# uno-level-shifter-v2.net
KiCad netlist of a schematic drawn in EAGLE
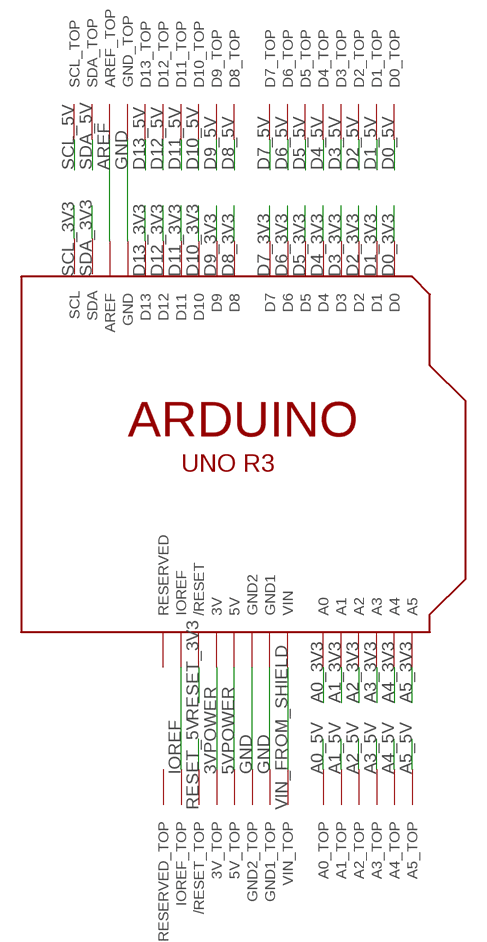
[diagram p0: schematic, sheet 1]
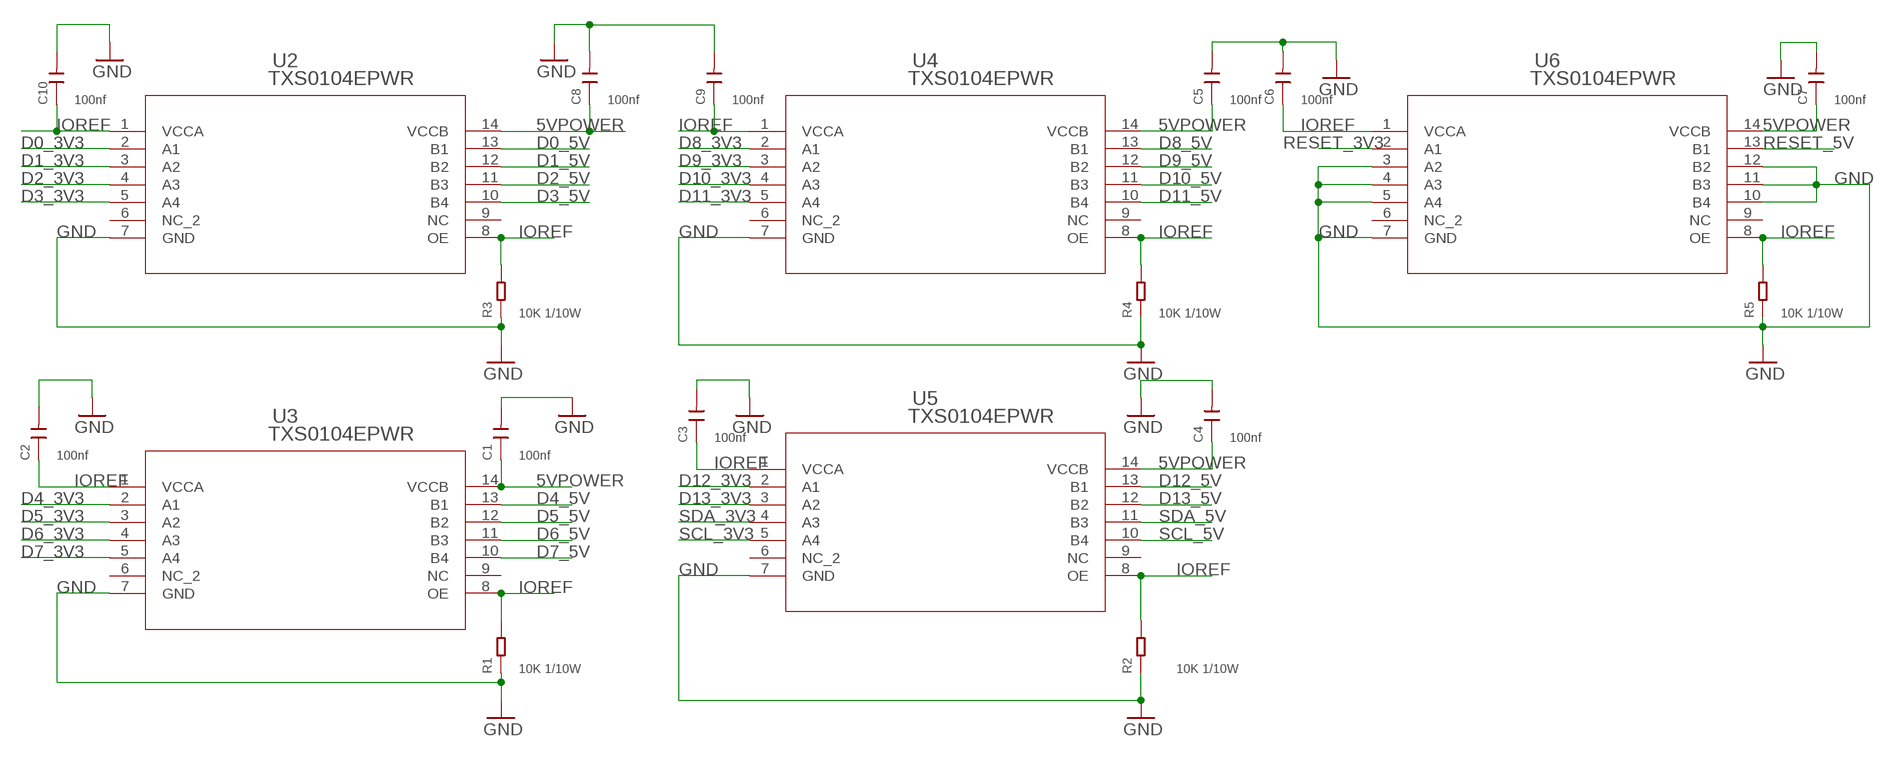
[diagram p1: schematic, sheet 2]
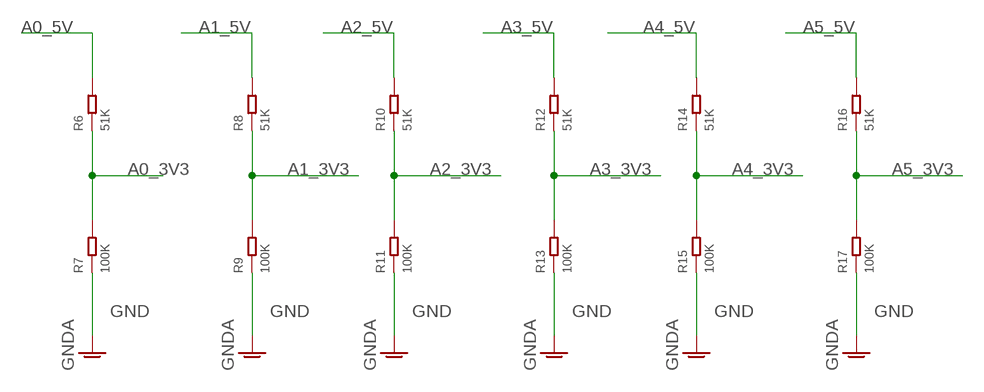
[diagram p2: schematic, sheet 3]

(export (version "E")
  (design (tool "Eeschema 10.0.6"))
  (components
    (comp (ref "R6")
      (value "51K")
      (footprint "eagle-import:R0603")
      (fields (field (name "MPN") "RC0603FR-071K5L"))
      (libsource (lib "eagle-import") (part "SMD-RES-51K-1%-1/10W(0603)"))
    )
    (comp (ref "R7")
      (value "100K")
      (footprint "eagle-import:R0603")
      (fields (field (name "MPN") "RC0603FR-07100KL"))
      (libsource (lib "eagle-import") (part "SMD-RES-100K-1%-1/10W(0603)"))
    )
    (comp (ref "R8")
      (value "51K")
      (footprint "eagle-import:R0603")
      (fields (field (name "MPN") "RC0603FR-071K5L"))
      (libsource (lib "eagle-import") (part "SMD-RES-51K-1%-1/10W(0603)"))
    )
    (comp (ref "R9")
      (value "100K")
      (footprint "eagle-import:R0603")
      (fields (field (name "MPN") "RC0603FR-07100KL"))
      (libsource (lib "eagle-import") (part "SMD-RES-100K-1%-1/10W(0603)"))
    )
    (comp (ref "R10")
      (value "51K")
      (footprint "eagle-import:R0603")
      (fields (field (name "MPN") "RC0603FR-071K5L"))
      (libsource (lib "eagle-import") (part "SMD-RES-51K-1%-1/10W(0603)"))
    )
    (comp (ref "R11")
      (value "100K")
      (footprint "eagle-import:R0603")
      (fields (field (name "MPN") "RC0603FR-07100KL"))
      (libsource (lib "eagle-import") (part "SMD-RES-100K-1%-1/10W(0603)"))
    )
    (comp (ref "R12")
      (value "51K")
      (footprint "eagle-import:R0603")
      (fields (field (name "MPN") "RC0603FR-071K5L"))
      (libsource (lib "eagle-import") (part "SMD-RES-51K-1%-1/10W(0603)"))
    )
    (comp (ref "R13")
      (value "100K")
      (footprint "eagle-import:R0603")
      (fields (field (name "MPN") "RC0603FR-07100KL"))
      (libsource (lib "eagle-import") (part "SMD-RES-100K-1%-1/10W(0603)"))
    )
    (comp (ref "R14")
      (value "51K")
      (footprint "eagle-import:R0603")
      (fields (field (name "MPN") "RC0603FR-071K5L"))
      (libsource (lib "eagle-import") (part "SMD-RES-51K-1%-1/10W(0603)"))
    )
    (comp (ref "R15")
      (value "100K")
      (footprint "eagle-import:R0603")
      (fields (field (name "MPN") "RC0603FR-07100KL"))
      (libsource (lib "eagle-import") (part "SMD-RES-100K-1%-1/10W(0603)"))
    )
    (comp (ref "R16")
      (value "51K")
      (footprint "eagle-import:R0603")
      (fields (field (name "MPN") "RC0603FR-071K5L"))
      (libsource (lib "eagle-import") (part "SMD-RES-51K-1%-1/10W(0603)"))
    )
    (comp (ref "R17")
      (value "100K")
      (footprint "eagle-import:R0603")
      (fields (field (name "MPN") "RC0603FR-07100KL"))
      (libsource (lib "eagle-import") (part "SMD-RES-100K-1%-1/10W(0603)"))
    )
    (comp (ref "U1")
      (value "ARDUINOR3-DIMENSION")
      (footprint "eagle-import:ARDUINOR3")
      (libsource (lib "eagle-import") (part "ARDUINOR3-DIMENSION"))
    )
    (comp (ref "C1")
      (value "100nf")
      (footprint "eagle-import:C0603")
      (fields (field (name "MPN") "CC0603KRX7R9BB104"))
      (libsource (lib "eagle-import") (part "CERAMIC-100NF-50V-10%-X7R(0603)"))
    )
    (comp (ref "C2")
      (value "100nf")
      (footprint "eagle-import:C0603")
      (fields (field (name "MPN") "CC0603KRX7R9BB104"))
      (libsource (lib "eagle-import") (part "CERAMIC-100NF-50V-10%-X7R(0603)"))
    )
    (comp (ref "C3")
      (value "100nf")
      (footprint "eagle-import:C0603")
      (fields (field (name "MPN") "CC0603KRX7R9BB104"))
      (libsource (lib "eagle-import") (part "CERAMIC-100NF-50V-10%-X7R(0603)"))
    )
    (comp (ref "C4")
      (value "100nf")
      (footprint "eagle-import:C0603")
      (fields (field (name "MPN") "CC0603KRX7R9BB104"))
      (libsource (lib "eagle-import") (part "CERAMIC-100NF-50V-10%-X7R(0603)"))
    )
    (comp (ref "C5")
      (value "100nf")
      (footprint "eagle-import:C0603")
      (fields (field (name "MPN") "CC0603KRX7R9BB104"))
      (libsource (lib "eagle-import") (part "CERAMIC-100NF-50V-10%-X7R(0603)"))
    )
    (comp (ref "C6")
      (value "100nf")
      (footprint "eagle-import:C0603")
      (fields (field (name "MPN") "CC0603KRX7R9BB104"))
      (libsource (lib "eagle-import") (part "CERAMIC-100NF-50V-10%-X7R(0603)"))
    )
    (comp (ref "C7")
      (value "100nf")
      (footprint "eagle-import:C0603")
      (fields (field (name "MPN") "CC0603KRX7R9BB104"))
      (libsource (lib "eagle-import") (part "CERAMIC-100NF-50V-10%-X7R(0603)"))
    )
    (comp (ref "C8")
      (value "100nf")
      (footprint "eagle-import:C0603")
      (fields (field (name "MPN") "CC0603KRX7R9BB104"))
      (libsource (lib "eagle-import") (part "CERAMIC-100NF-50V-10%-X7R(0603)"))
    )
    (comp (ref "C9")
      (value "100nf")
      (footprint "eagle-import:C0603")
      (fields (field (name "MPN") "CC0603KRX7R9BB104"))
      (libsource (lib "eagle-import") (part "CERAMIC-100NF-50V-10%-X7R(0603)"))
    )
    (comp (ref "C10")
      (value "100nf")
      (footprint "eagle-import:C0603")
      (fields (field (name "MPN") "CC0603KRX7R9BB104"))
      (libsource (lib "eagle-import") (part "CERAMIC-100NF-50V-10%-X7R(0603)"))
    )
    (comp (ref "R1")
      (value "10K 1/10W")
      (footprint "eagle-import:R0603")
      (fields (field (name "MPN") "RC0603JR-0710KL"))
      (libsource (lib "eagle-import") (part "SMD-RES-10K-5%-1/10W(0603)"))
    )
    (comp (ref "R2")
      (value "10K 1/10W")
      (footprint "eagle-import:R0603")
      (fields (field (name "MPN") "RC0603JR-0710KL"))
      (libsource (lib "eagle-import") (part "SMD-RES-10K-5%-1/10W(0603)"))
    )
    (comp (ref "R3")
      (value "10K 1/10W")
      (footprint "eagle-import:R0603")
      (fields (field (name "MPN") "RC0603JR-0710KL"))
      (libsource (lib "eagle-import") (part "SMD-RES-10K-5%-1/10W(0603)"))
    )
    (comp (ref "R4")
      (value "10K 1/10W")
      (footprint "eagle-import:R0603")
      (fields (field (name "MPN") "RC0603JR-0710KL"))
      (libsource (lib "eagle-import") (part "SMD-RES-10K-5%-1/10W(0603)"))
    )
    (comp (ref "R5")
      (value "10K 1/10W")
      (footprint "eagle-import:R0603")
      (fields (field (name "MPN") "RC0603JR-0710KL"))
      (libsource (lib "eagle-import") (part "SMD-RES-10K-5%-1/10W(0603)"))
    )
    (comp (ref "U2")
      (value "TXS0104EPWR")
      (footprint "eagle-import:PW14")
      (fields
        (field (name "GENERIC_PART_NUMBER") "TXS0104E")
        (field (name "MANUFACTURER") "Texas Instruments")
      )
      (libsource (lib "eagle-import") (part "TXS0104EPWR"))
    )
    (comp (ref "U3")
      (value "TXS0104EPWR")
      (footprint "eagle-import:PW14")
      (fields
        (field (name "GENERIC_PART_NUMBER") "TXS0104E")
        (field (name "MANUFACTURER") "Texas Instruments")
      )
      (libsource (lib "eagle-import") (part "TXS0104EPWR"))
    )
    (comp (ref "U4")
      (value "TXS0104EPWR")
      (footprint "eagle-import:PW14")
      (fields
        (field (name "GENERIC_PART_NUMBER") "TXS0104E")
        (field (name "MANUFACTURER") "Texas Instruments")
      )
      (libsource (lib "eagle-import") (part "TXS0104EPWR"))
    )
    (comp (ref "U5")
      (value "TXS0104EPWR")
      (footprint "eagle-import:PW14")
      (fields
        (field (name "GENERIC_PART_NUMBER") "TXS0104E")
        (field (name "MANUFACTURER") "Texas Instruments")
      )
      (libsource (lib "eagle-import") (part "TXS0104EPWR"))
    )
    (comp (ref "U6")
      (value "TXS0104EPWR")
      (footprint "eagle-import:PW14")
      (fields
        (field (name "GENERIC_PART_NUMBER") "TXS0104E")
        (field (name "MANUFACTURER") "Texas Instruments")
      )
      (libsource (lib "eagle-import") (part "TXS0104EPWR"))
    )
  )
  (nets
    (net (code "1") (name "3VPOWER") (class "Default")
      (node (ref "U1") (pin "3V") (pinfunction "3V_3V") (pintype "power_in"))
      (node (ref "U1") (pin "3V_TOP") (pinfunction "3V_TOP_3V_TOP") (pintype "power_in"))
    )
    (net (code "2") (name "5VPOWER") (class "Default")
      (node (ref "C1") (pin "1") (pinfunction "1_1") (pintype "passive"))
      (node (ref "C4") (pin "1") (pinfunction "1_1") (pintype "passive"))
      (node (ref "C5") (pin "1") (pinfunction "1_1") (pintype "passive"))
      (node (ref "C7") (pin "1") (pinfunction "1_1") (pintype "passive"))
      (node (ref "C8") (pin "1") (pinfunction "1_1") (pintype "passive"))
      (node (ref "U1") (pin "5V") (pinfunction "5V_5V") (pintype "power_in"))
      (node (ref "U1") (pin "5V_TOP") (pinfunction "5V_TOP_5V_TOP") (pintype "power_in"))
      (node (ref "U2") (pin "14") (pinfunction "VCCB_14") (pintype "power_in"))
      (node (ref "U3") (pin "14") (pinfunction "VCCB_14") (pintype "power_in"))
      (node (ref "U4") (pin "14") (pinfunction "VCCB_14") (pintype "power_in"))
      (node (ref "U5") (pin "14") (pinfunction "VCCB_14") (pintype "power_in"))
      (node (ref "U6") (pin "14") (pinfunction "VCCB_14") (pintype "power_in"))
    )
    (net (code "3") (name "A0_3V3") (class "Default")
      (node (ref "R6") (pin "1") (pinfunction "1_1") (pintype "passive"))
      (node (ref "R7") (pin "2") (pinfunction "2_2") (pintype "passive"))
      (node (ref "U1") (pin "A0") (pinfunction "A0_A0") (pintype "bidirectional"))
    )
    (net (code "4") (name "A0_5V") (class "Default")
      (node (ref "R6") (pin "2") (pinfunction "2_2") (pintype "passive"))
      (node (ref "U1") (pin "A0_TOP") (pinfunction "A0_TOP_A0_TOP") (pintype "bidirectional"))
    )
    (net (code "5") (name "A1_3V3") (class "Default")
      (node (ref "R8") (pin "1") (pinfunction "1_1") (pintype "passive"))
      (node (ref "R9") (pin "2") (pinfunction "2_2") (pintype "passive"))
      (node (ref "U1") (pin "A1") (pinfunction "A1_A1") (pintype "bidirectional"))
    )
    (net (code "6") (name "A1_5V") (class "Default")
      (node (ref "R8") (pin "2") (pinfunction "2_2") (pintype "passive"))
      (node (ref "U1") (pin "A1_TOP") (pinfunction "A1_TOP_A1_TOP") (pintype "bidirectional"))
    )
    (net (code "7") (name "A2_3V3") (class "Default")
      (node (ref "R10") (pin "1") (pinfunction "1_1") (pintype "passive"))
      (node (ref "R11") (pin "2") (pinfunction "2_2") (pintype "passive"))
      (node (ref "U1") (pin "A2") (pinfunction "A2_A2") (pintype "bidirectional"))
    )
    (net (code "8") (name "A2_5V") (class "Default")
      (node (ref "R10") (pin "2") (pinfunction "2_2") (pintype "passive"))
      (node (ref "U1") (pin "A2_TOP") (pinfunction "A2_TOP_A2_TOP") (pintype "bidirectional"))
    )
    (net (code "9") (name "A3_3V3") (class "Default")
      (node (ref "R12") (pin "1") (pinfunction "1_1") (pintype "passive"))
      (node (ref "R13") (pin "2") (pinfunction "2_2") (pintype "passive"))
      (node (ref "U1") (pin "A3") (pinfunction "A3_A3") (pintype "bidirectional"))
    )
    (net (code "10") (name "A3_5V") (class "Default")
      (node (ref "R12") (pin "2") (pinfunction "2_2") (pintype "passive"))
      (node (ref "U1") (pin "A3_TOP") (pinfunction "A3_TOP_A3_TOP") (pintype "bidirectional"))
    )
    (net (code "11") (name "A4_3V3") (class "Default")
      (node (ref "R14") (pin "1") (pinfunction "1_1") (pintype "passive"))
      (node (ref "R15") (pin "2") (pinfunction "2_2") (pintype "passive"))
      (node (ref "U1") (pin "A4") (pinfunction "A4_A4") (pintype "bidirectional"))
    )
    (net (code "12") (name "A4_5V") (class "Default")
      (node (ref "R14") (pin "2") (pinfunction "2_2") (pintype "passive"))
      (node (ref "U1") (pin "A4_TOP") (pinfunction "A4_TOP_A4_TOP") (pintype "bidirectional"))
    )
    (net (code "13") (name "A5_3V3") (class "Default")
      (node (ref "R16") (pin "1") (pinfunction "1_1") (pintype "passive"))
      (node (ref "R17") (pin "2") (pinfunction "2_2") (pintype "passive"))
      (node (ref "U1") (pin "A5") (pinfunction "A5_A5") (pintype "bidirectional"))
    )
    (net (code "14") (name "A5_5V") (class "Default")
      (node (ref "R16") (pin "2") (pinfunction "2_2") (pintype "passive"))
      (node (ref "U1") (pin "A5_TOP") (pinfunction "A5_TOP_A5_TOP") (pintype "bidirectional"))
    )
    (net (code "15") (name "AREF") (class "Default")
      (node (ref "U1") (pin "AREF") (pinfunction "AREF_AREF") (pintype "bidirectional"))
      (node (ref "U1") (pin "AREF_TOP") (pinfunction "AREF_TOP_AREF_TOP") (pintype "bidirectional"))
    )
    (net (code "16") (name "D0_3V3") (class "Default")
      (node (ref "U1") (pin "D0") (pinfunction "D0_D0") (pintype "bidirectional"))
      (node (ref "U2") (pin "2") (pinfunction "A1_2") (pintype "bidirectional"))
    )
    (net (code "17") (name "D0_5V") (class "Default")
      (node (ref "U1") (pin "D0_TOP") (pinfunction "D0_TOP_D0_TOP") (pintype "bidirectional"))
      (node (ref "U2") (pin "13") (pinfunction "B1_13") (pintype "bidirectional"))
    )
    (net (code "18") (name "D1_3V3") (class "Default")
      (node (ref "U1") (pin "D1") (pinfunction "D1_D1") (pintype "bidirectional"))
      (node (ref "U2") (pin "3") (pinfunction "A2_3") (pintype "bidirectional"))
    )
    (net (code "19") (name "D1_5V") (class "Default")
      (node (ref "U1") (pin "D1_TOP") (pinfunction "D1_TOP_D1_TOP") (pintype "bidirectional"))
      (node (ref "U2") (pin "12") (pinfunction "B2_12") (pintype "bidirectional"))
    )
    (net (code "20") (name "D2_3V3") (class "Default")
      (node (ref "U1") (pin "D2") (pinfunction "D2_D2") (pintype "bidirectional"))
      (node (ref "U2") (pin "4") (pinfunction "A3_4") (pintype "bidirectional"))
    )
    (net (code "21") (name "D2_5V") (class "Default")
      (node (ref "U1") (pin "D2_TOP") (pinfunction "D2_TOP_D2_TOP") (pintype "bidirectional"))
      (node (ref "U2") (pin "11") (pinfunction "B3_11") (pintype "bidirectional"))
    )
    (net (code "22") (name "D3_3V3") (class "Default")
      (node (ref "U1") (pin "D3") (pinfunction "D3_D3") (pintype "bidirectional"))
      (node (ref "U2") (pin "5") (pinfunction "A4_5") (pintype "bidirectional"))
    )
    (net (code "23") (name "D3_5V") (class "Default")
      (node (ref "U1") (pin "D3_TOP") (pinfunction "D3_TOP_D3_TOP") (pintype "bidirectional"))
      (node (ref "U2") (pin "10") (pinfunction "B4_10") (pintype "bidirectional"))
    )
    (net (code "24") (name "D4_3V3") (class "Default")
      (node (ref "U1") (pin "D4") (pinfunction "D4_D4") (pintype "bidirectional"))
      (node (ref "U3") (pin "2") (pinfunction "A1_2") (pintype "bidirectional"))
    )
    (net (code "25") (name "D4_5V") (class "Default")
      (node (ref "U1") (pin "D4_TOP") (pinfunction "D4_TOP_D4_TOP") (pintype "bidirectional"))
      (node (ref "U3") (pin "13") (pinfunction "B1_13") (pintype "bidirectional"))
    )
    (net (code "26") (name "D5_3V3") (class "Default")
      (node (ref "U1") (pin "D5") (pinfunction "D5_D5") (pintype "bidirectional"))
      (node (ref "U3") (pin "3") (pinfunction "A2_3") (pintype "bidirectional"))
    )
    (net (code "27") (name "D5_5V") (class "Default")
      (node (ref "U1") (pin "D5_TOP") (pinfunction "D5_TOP_D5_TOP") (pintype "bidirectional"))
      (node (ref "U3") (pin "12") (pinfunction "B2_12") (pintype "bidirectional"))
    )
    (net (code "28") (name "D6_3V3") (class "Default")
      (node (ref "U1") (pin "D6") (pinfunction "D6_D6") (pintype "bidirectional"))
      (node (ref "U3") (pin "4") (pinfunction "A3_4") (pintype "bidirectional"))
    )
    (net (code "29") (name "D6_5V") (class "Default")
      (node (ref "U1") (pin "D6_TOP") (pinfunction "D6_TOP_D6_TOP") (pintype "bidirectional"))
      (node (ref "U3") (pin "11") (pinfunction "B3_11") (pintype "bidirectional"))
    )
    (net (code "30") (name "D7_3V3") (class "Default")
      (node (ref "U1") (pin "D7") (pinfunction "D7_D7") (pintype "bidirectional"))
      (node (ref "U3") (pin "5") (pinfunction "A4_5") (pintype "bidirectional"))
    )
    (net (code "31") (name "D7_5V") (class "Default")
      (node (ref "U1") (pin "D7_TOP") (pinfunction "D7_TOP_D7_TOP") (pintype "bidirectional"))
      (node (ref "U3") (pin "10") (pinfunction "B4_10") (pintype "bidirectional"))
    )
    (net (code "32") (name "D8_3V3") (class "Default")
      (node (ref "U1") (pin "D8") (pinfunction "D8_D8") (pintype "bidirectional"))
      (node (ref "U4") (pin "2") (pinfunction "A1_2") (pintype "bidirectional"))
    )
    (net (code "33") (name "D8_5V") (class "Default")
      (node (ref "U1") (pin "D8_TOP") (pinfunction "D8_TOP_D8_TOP") (pintype "bidirectional"))
      (node (ref "U4") (pin "13") (pinfunction "B1_13") (pintype "bidirectional"))
    )
    (net (code "34") (name "D9_3V3") (class "Default")
      (node (ref "U1") (pin "D9") (pinfunction "D9_D9") (pintype "bidirectional"))
      (node (ref "U4") (pin "3") (pinfunction "A2_3") (pintype "bidirectional"))
    )
    (net (code "35") (name "D9_5V") (class "Default")
      (node (ref "U1") (pin "D9_TOP") (pinfunction "D9_TOP_D9_TOP") (pintype "bidirectional"))
      (node (ref "U4") (pin "12") (pinfunction "B2_12") (pintype "bidirectional"))
    )
    (net (code "36") (name "D10_3V3") (class "Default")
      (node (ref "U1") (pin "D10") (pinfunction "D10_D10") (pintype "bidirectional"))
      (node (ref "U4") (pin "4") (pinfunction "A3_4") (pintype "bidirectional"))
    )
    (net (code "37") (name "D10_5V") (class "Default")
      (node (ref "U1") (pin "D10_TOP") (pinfunction "D10_TOP_D10_TOP") (pintype "bidirectional"))
      (node (ref "U4") (pin "11") (pinfunction "B3_11") (pintype "bidirectional"))
    )
    (net (code "38") (name "D11_3V3") (class "Default")
      (node (ref "U1") (pin "D11") (pinfunction "D11_D11") (pintype "bidirectional"))
      (node (ref "U4") (pin "5") (pinfunction "A4_5") (pintype "bidirectional"))
    )
    (net (code "39") (name "D11_5V") (class "Default")
      (node (ref "U1") (pin "D11_TOP") (pinfunction "D11_TOP_D11_TOP") (pintype "bidirectional"))
      (node (ref "U4") (pin "10") (pinfunction "B4_10") (pintype "bidirectional"))
    )
    (net (code "40") (name "D12_3V3") (class "Default")
      (node (ref "U1") (pin "D12") (pinfunction "D12_D12") (pintype "bidirectional"))
      (node (ref "U5") (pin "2") (pinfunction "A1_2") (pintype "bidirectional"))
    )
    (net (code "41") (name "D12_5V") (class "Default")
      (node (ref "U1") (pin "D12_TOP") (pinfunction "D12_TOP_D12_TOP") (pintype "bidirectional"))
      (node (ref "U5") (pin "13") (pinfunction "B1_13") (pintype "bidirectional"))
    )
    (net (code "42") (name "D13_3V3") (class "Default")
      (node (ref "U1") (pin "D13") (pinfunction "D13_D13") (pintype "bidirectional"))
      (node (ref "U5") (pin "3") (pinfunction "A2_3") (pintype "bidirectional"))
    )
    (net (code "43") (name "D13_5V") (class "Default")
      (node (ref "U1") (pin "D13_TOP") (pinfunction "D13_TOP_D13_TOP") (pintype "bidirectional"))
      (node (ref "U5") (pin "12") (pinfunction "B2_12") (pintype "bidirectional"))
    )
    (net (code "44") (name "GND") (class "Default")
      (node (ref "C1") (pin "2") (pinfunction "2_2") (pintype "passive"))
      (node (ref "C10") (pin "2") (pinfunction "2_2") (pintype "passive"))
      (node (ref "C2") (pin "2") (pinfunction "2_2") (pintype "passive"))
      (node (ref "C3") (pin "2") (pinfunction "2_2") (pintype "passive"))
      (node (ref "C4") (pin "2") (pinfunction "2_2") (pintype "passive"))
      (node (ref "C5") (pin "2") (pinfunction "2_2") (pintype "passive"))
      (node (ref "C6") (pin "2") (pinfunction "2_2") (pintype "passive"))
      (node (ref "C7") (pin "2") (pinfunction "2_2") (pintype "passive"))
      (node (ref "C8") (pin "2") (pinfunction "2_2") (pintype "passive"))
      (node (ref "C9") (pin "2") (pinfunction "2_2") (pintype "passive"))
      (node (ref "R1") (pin "1") (pinfunction "1_1") (pintype "passive"))
      (node (ref "R11") (pin "1") (pinfunction "1_1") (pintype "passive"))
      (node (ref "R13") (pin "1") (pinfunction "1_1") (pintype "passive"))
      (node (ref "R15") (pin "1") (pinfunction "1_1") (pintype "passive"))
      (node (ref "R17") (pin "1") (pinfunction "1_1") (pintype "passive"))
      (node (ref "R2") (pin "1") (pinfunction "1_1") (pintype "passive"))
      (node (ref "R3") (pin "1") (pinfunction "1_1") (pintype "passive"))
      (node (ref "R4") (pin "1") (pinfunction "1_1") (pintype "passive"))
      (node (ref "R5") (pin "1") (pinfunction "1_1") (pintype "passive"))
      (node (ref "R7") (pin "1") (pinfunction "1_1") (pintype "passive"))
      (node (ref "R9") (pin "1") (pinfunction "1_1") (pintype "passive"))
      (node (ref "U1") (pin "GND") (pinfunction "GND_GND") (pintype "power_in"))
      (node (ref "U1") (pin "GND1") (pinfunction "GND1_GND1") (pintype "power_in"))
      (node (ref "U1") (pin "GND1_TOP") (pinfunction "GND1_TOP_GND1_TOP") (pintype "power_in"))
      (node (ref "U1") (pin "GND2") (pinfunction "GND2_GND2") (pintype "power_in"))
      (node (ref "U1") (pin "GND2_TOP") (pinfunction "GND2_TOP_GND2_TOP") (pintype "power_in"))
      (node (ref "U1") (pin "GND_TOP") (pinfunction "GND_TOP_GND_TOP") (pintype "power_in"))
      (node (ref "U2") (pin "7") (pinfunction "GND_7") (pintype "power_in"))
      (node (ref "U3") (pin "7") (pinfunction "GND_7") (pintype "power_in"))
      (node (ref "U4") (pin "7") (pinfunction "GND_7") (pintype "power_in"))
      (node (ref "U5") (pin "7") (pinfunction "GND_7") (pintype "power_in"))
      (node (ref "U6") (pin "10") (pinfunction "B4_10") (pintype "bidirectional"))
      (node (ref "U6") (pin "11") (pinfunction "B3_11") (pintype "bidirectional"))
      (node (ref "U6") (pin "12") (pinfunction "B2_12") (pintype "bidirectional"))
      (node (ref "U6") (pin "3") (pinfunction "A2_3") (pintype "bidirectional"))
      (node (ref "U6") (pin "4") (pinfunction "A3_4") (pintype "bidirectional"))
      (node (ref "U6") (pin "5") (pinfunction "A4_5") (pintype "bidirectional"))
      (node (ref "U6") (pin "7") (pinfunction "GND_7") (pintype "power_in"))
    )
    (net (code "45") (name "IOREF") (class "Default")
      (node (ref "C10") (pin "1") (pinfunction "1_1") (pintype "passive"))
      (node (ref "C2") (pin "1") (pinfunction "1_1") (pintype "passive"))
      (node (ref "C3") (pin "1") (pinfunction "1_1") (pintype "passive"))
      (node (ref "C6") (pin "1") (pinfunction "1_1") (pintype "passive"))
      (node (ref "C9") (pin "1") (pinfunction "1_1") (pintype "passive"))
      (node (ref "R1") (pin "2") (pinfunction "2_2") (pintype "passive"))
      (node (ref "R2") (pin "2") (pinfunction "2_2") (pintype "passive"))
      (node (ref "R3") (pin "2") (pinfunction "2_2") (pintype "passive"))
      (node (ref "R4") (pin "2") (pinfunction "2_2") (pintype "passive"))
      (node (ref "R5") (pin "2") (pinfunction "2_2") (pintype "passive"))
      (node (ref "U1") (pin "IOREF") (pinfunction "IOREF_IOREF") (pintype "output"))
      (node (ref "U1") (pin "IOREF_TOP") (pinfunction "IOREF_TOP_IOREF_TOP") (pintype "output"))
      (node (ref "U2") (pin "1") (pinfunction "VCCA_1") (pintype "power_in"))
      (node (ref "U2") (pin "8") (pinfunction "OE_8") (pintype "output"))
      (node (ref "U3") (pin "1") (pinfunction "VCCA_1") (pintype "power_in"))
      (node (ref "U3") (pin "8") (pinfunction "OE_8") (pintype "output"))
      (node (ref "U4") (pin "1") (pinfunction "VCCA_1") (pintype "power_in"))
      (node (ref "U4") (pin "8") (pinfunction "OE_8") (pintype "output"))
      (node (ref "U5") (pin "1") (pinfunction "VCCA_1") (pintype "power_in"))
      (node (ref "U5") (pin "8") (pinfunction "OE_8") (pintype "output"))
      (node (ref "U6") (pin "1") (pinfunction "VCCA_1") (pintype "power_in"))
      (node (ref "U6") (pin "8") (pinfunction "OE_8") (pintype "output"))
    )
    (net (code "46") (name "RESET_3V3") (class "Default")
      (node (ref "U1") (pin "RESET") (pinfunction "/RESET_RESET") (pintype "bidirectional"))
      (node (ref "U6") (pin "2") (pinfunction "A1_2") (pintype "bidirectional"))
    )
    (net (code "47") (name "RESET_5V") (class "Default")
      (node (ref "U1") (pin "RESET_TOP") (pinfunction "/RESET_TOP_RESET_TOP") (pintype "bidirectional"))
      (node (ref "U6") (pin "13") (pinfunction "B1_13") (pintype "bidirectional"))
    )
    (net (code "48") (name "SCL_3V3") (class "Default")
      (node (ref "U1") (pin "SCL") (pinfunction "SCL_SCL") (pintype "bidirectional"))
      (node (ref "U5") (pin "5") (pinfunction "A4_5") (pintype "bidirectional"))
    )
    (net (code "49") (name "SCL_5V") (class "Default")
      (node (ref "U1") (pin "SCL_TOP") (pinfunction "SCL_TOP_SCL_TOP") (pintype "bidirectional"))
      (node (ref "U5") (pin "10") (pinfunction "B4_10") (pintype "bidirectional"))
    )
    (net (code "50") (name "SDA_3V3") (class "Default")
      (node (ref "U1") (pin "SDA") (pinfunction "SDA_SDA") (pintype "bidirectional"))
      (node (ref "U5") (pin "4") (pinfunction "A3_4") (pintype "bidirectional"))
    )
    (net (code "51") (name "SDA_5V") (class "Default")
      (node (ref "U1") (pin "SDA_TOP") (pinfunction "SDA_TOP_SDA_TOP") (pintype "bidirectional"))
      (node (ref "U5") (pin "11") (pinfunction "B3_11") (pintype "bidirectional"))
    )
    (net (code "52") (name "VIN_FROM_SHIELD") (class "Default")
      (node (ref "U1") (pin "VIN") (pinfunction "VIN_VIN") (pintype "power_in"))
      (node (ref "U1") (pin "VIN_TOP") (pinfunction "VIN_TOP_VIN_TOP") (pintype "power_in"))
    )
    (net (code "53") (name "unconnected-(U1-PadRESERVED)") (class "Default")
      (node (ref "U1") (pin "RESERVED") (pinfunction "RESERVED_RESERVED") (pintype "no_connect"))
    )
    (net (code "54") (name "unconnected-(U1-PadRESERVED_TOP)") (class "Default")
      (node (ref "U1") (pin "RESERVED_TOP") (pinfunction "RESERVED_TOP_RESERVED_TOP") (pintype "no_connect"))
    )
    (net (code "55") (name "unconnected-(U2-NC-Pad9)") (class "Default")
      (node (ref "U2") (pin "9") (pinfunction "NC_9") (pintype "passive"))
    )
    (net (code "56") (name "unconnected-(U2-NC_2-Pad6)") (class "Default")
      (node (ref "U2") (pin "6") (pinfunction "NC_2_6") (pintype "passive"))
    )
    (net (code "57") (name "unconnected-(U3-NC-Pad9)") (class "Default")
      (node (ref "U3") (pin "9") (pinfunction "NC_9") (pintype "passive"))
    )
    (net (code "58") (name "unconnected-(U3-NC_2-Pad6)") (class "Default")
      (node (ref "U3") (pin "6") (pinfunction "NC_2_6") (pintype "passive"))
    )
    (net (code "59") (name "unconnected-(U4-NC-Pad9)") (class "Default")
      (node (ref "U4") (pin "9") (pinfunction "NC_9") (pintype "passive"))
    )
    (net (code "60") (name "unconnected-(U4-NC_2-Pad6)") (class "Default")
      (node (ref "U4") (pin "6") (pinfunction "NC_2_6") (pintype "passive"))
    )
    (net (code "61") (name "unconnected-(U5-NC-Pad9)") (class "Default")
      (node (ref "U5") (pin "9") (pinfunction "NC_9") (pintype "passive"))
    )
    (net (code "62") (name "unconnected-(U5-NC_2-Pad6)") (class "Default")
      (node (ref "U5") (pin "6") (pinfunction "NC_2_6") (pintype "passive"))
    )
    (net (code "63") (name "unconnected-(U6-NC-Pad9)") (class "Default")
      (node (ref "U6") (pin "9") (pinfunction "NC_9") (pintype "passive"))
    )
    (net (code "64") (name "unconnected-(U6-NC_2-Pad6)") (class "Default")
      (node (ref "U6") (pin "6") (pinfunction "NC_2_6") (pintype "passive"))
    )
  )
)
